# PowerLED_module.net
KiCad netlist of a schematic drawn in EAGLE
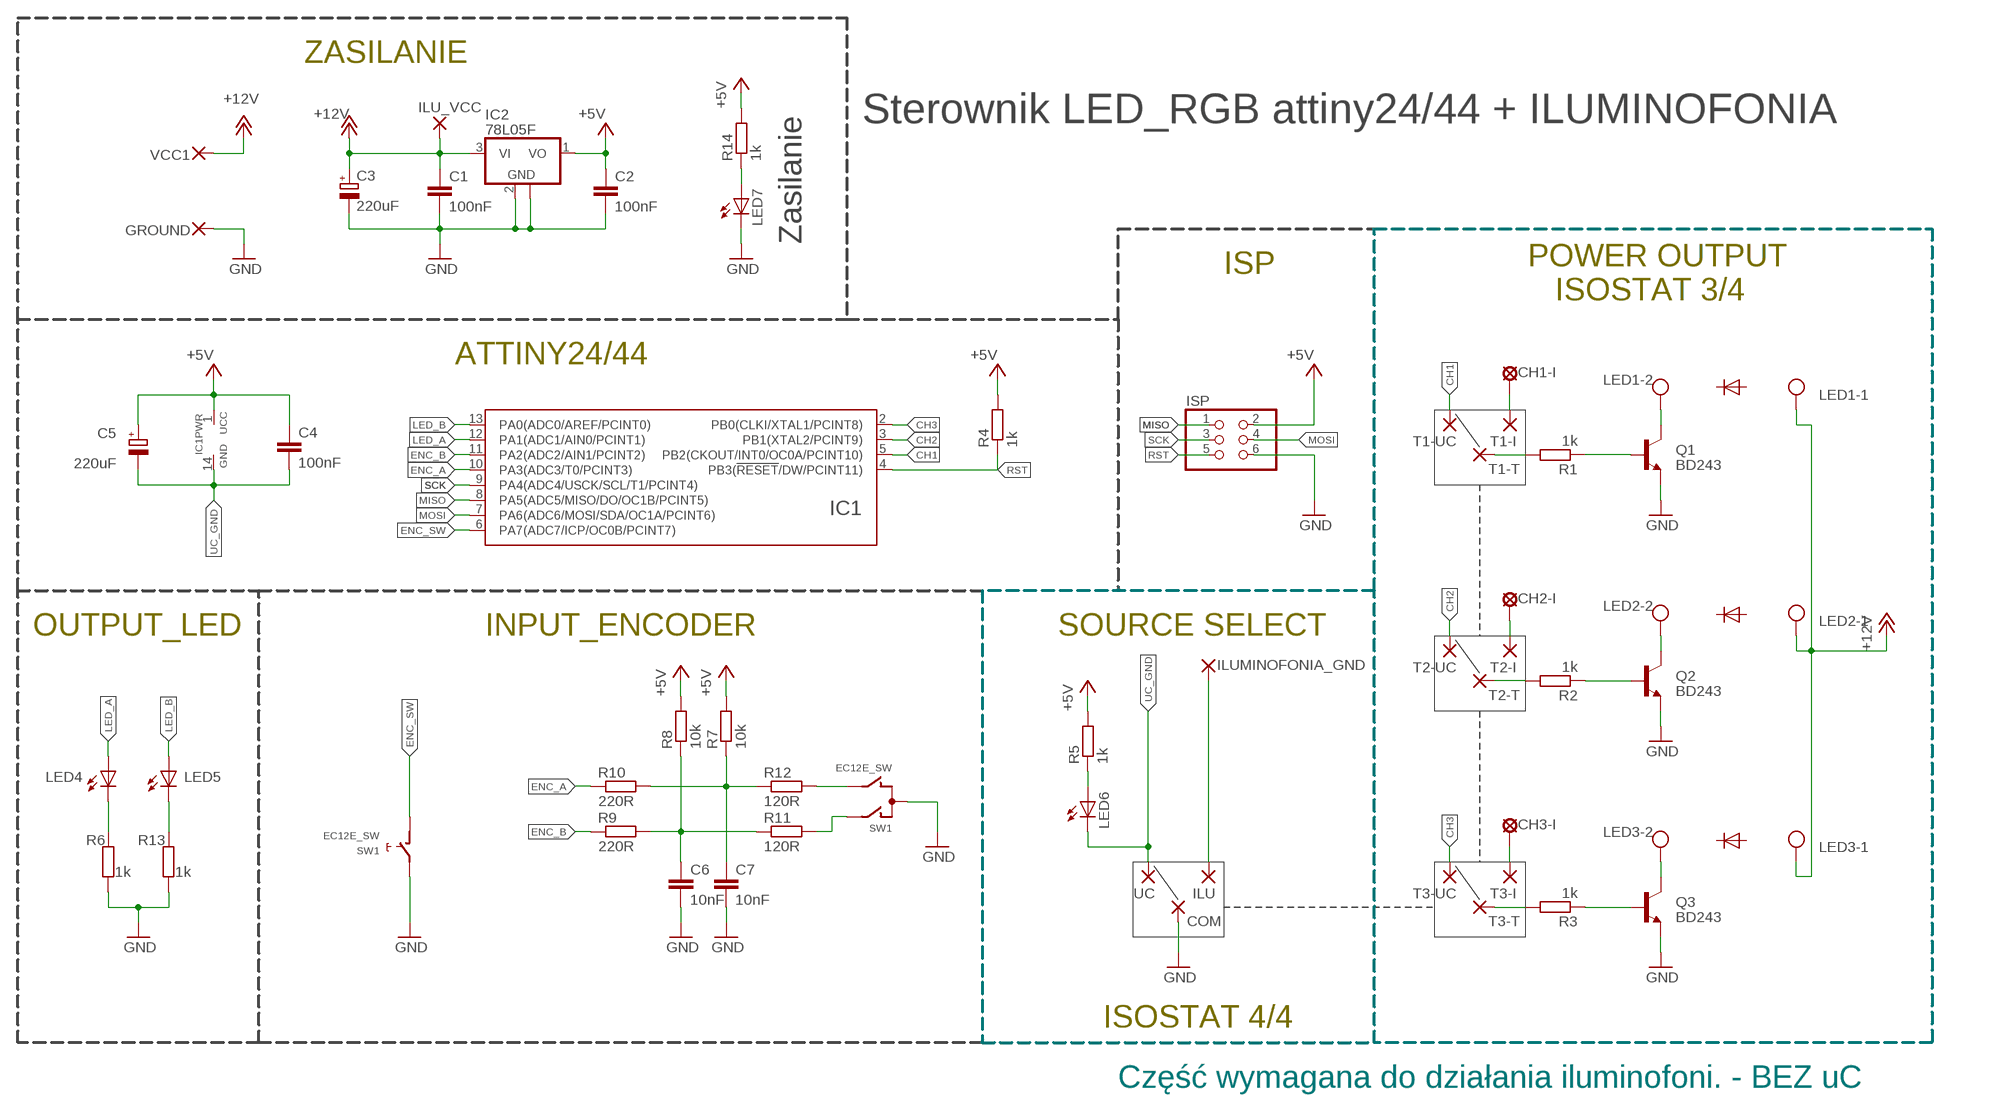
[diagram p0: schematic, sheet 1]

(export (version "E")
  (design (tool "Eeschema 10.0.6"))
  (components
    (comp (ref "C1")
      (value "100nF")
      (footprint "eagle-import:C50-45-75")
      (libsource (lib "eagle-import") (part "C-EU050-045-075"))
    )
    (comp (ref "C2")
      (value "100nF")
      (footprint "eagle-import:C50-45-75")
      (libsource (lib "eagle-import") (part "C-EU050-045-075"))
    )
    (comp (ref "C3")
      (value "220uF")
      (footprint "eagle-import:E2,5-6")
      (libsource (lib "eagle-import") (part "C-EU-POL'"))
    )
    (comp (ref "C4")
      (value "100nF")
      (footprint "eagle-import:C50-45-75")
      (libsource (lib "eagle-import") (part "C-EU050-045-075"))
    )
    (comp (ref "C5")
      (value "220uF")
      (footprint "eagle-import:E2,5-6")
      (libsource (lib "eagle-import") (part "C-EU-POL'"))
    )
    (comp (ref "C6")
      (value "10nF")
      (footprint "eagle-import:C50-45-75")
      (libsource (lib "eagle-import") (part "C-EU050-045-075"))
    )
    (comp (ref "C7")
      (value "10nF")
      (footprint "eagle-import:C50-45-75")
      (libsource (lib "eagle-import") (part "C-EU050-045-075"))
    )
    (comp (ref "CH1-I")
      (value "SE14")
      (footprint "eagle-import:SE14")
      (libsource (lib "eagle-import") (part "SE14"))
    )
    (comp (ref "CH2-I")
      (value "SE14")
      (footprint "eagle-import:SE14")
      (libsource (lib "eagle-import") (part "SE14"))
    )
    (comp (ref "CH3-I")
      (value "SE14")
      (footprint "eagle-import:SE14")
      (libsource (lib "eagle-import") (part "SE14"))
    )
    (comp (ref "COM")
      (value "1,6/0,9")
      (footprint "eagle-import:1,6_0,9")
      (libsource (lib "eagle-import") (part "1,6/0,9"))
    )
    (comp (ref "GROUND")
      (value "3,81/1,4")
      (footprint "eagle-import:3,81_1,4")
      (libsource (lib "eagle-import") (part "3,81/1,4"))
    )
    (comp (ref "IC1")
      (value "ATTINY24/44/84-SSU")
      (footprint "eagle-import:SOIC14")
      (libsource (lib "eagle-import") (part "ATTINY24/44/84-SSU"))
    )
    (comp (ref "IC2")
      (value "78L05F")
      (footprint "eagle-import:SOT89")
      (libsource (lib "eagle-import") (part "78LF05"))
    )
    (comp (ref "ILU")
      (value "1,6/0,9")
      (footprint "eagle-import:1,6_0,9")
      (libsource (lib "eagle-import") (part "1,6/0,9"))
    )
    (comp (ref "ILUMINOFONIA_GND")
      (value "3,81/1,4")
      (footprint "eagle-import:3,81_1,4")
      (libsource (lib "eagle-import") (part "3,81/1,4"))
    )
    (comp (ref "ILU_VCC")
      (value "3,81/1,4")
      (footprint "eagle-import:3,81_1,4")
      (libsource (lib "eagle-import") (part "3,81/1,4"))
    )
    (comp (ref "ISP")
      (value "PINHD-2X3")
      (footprint "eagle-import:2X03")
      (libsource (lib "eagle-import") (part "PINHD-2X3"))
    )
    (comp (ref "LED1")
      (value "AK300/2")
      (footprint "eagle-import:AK300_2")
      (libsource (lib "eagle-import") (part "AK300/2"))
    )
    (comp (ref "LED2")
      (value "AK300/2")
      (footprint "eagle-import:AK300_2")
      (libsource (lib "eagle-import") (part "AK300/2"))
    )
    (comp (ref "LED3")
      (value "AK300/2")
      (footprint "eagle-import:AK300_2")
      (libsource (lib "eagle-import") (part "AK300/2"))
    )
    (comp (ref "LED4")
      (value "LED5MM")
      (footprint "eagle-import:LED5MM")
      (libsource (lib "eagle-import") (part "LED5MM"))
    )
    (comp (ref "LED5")
      (value "LED5MM")
      (footprint "eagle-import:LED5MM")
      (libsource (lib "eagle-import") (part "LED5MM"))
    )
    (comp (ref "LED6")
      (value "LED5MM")
      (footprint "eagle-import:LED5MM")
      (libsource (lib "eagle-import") (part "LED5MM"))
    )
    (comp (ref "LED7")
      (value "LED5MM")
      (footprint "eagle-import:LED5MM")
      (libsource (lib "eagle-import") (part "LED5MM"))
    )
    (comp (ref "Q1")
      (value "BD243")
      (footprint "eagle-import:TO220")
      (libsource (lib "eagle-import") (part "BD243"))
    )
    (comp (ref "Q2")
      (value "BD243")
      (footprint "eagle-import:TO220")
      (libsource (lib "eagle-import") (part "BD243"))
    )
    (comp (ref "Q3")
      (value "BD243")
      (footprint "eagle-import:TO220")
      (libsource (lib "eagle-import") (part "BD243"))
    )
    (comp (ref "R1")
      (value "1k")
      (footprint "eagle-import:204_7")
      (libsource (lib "eagle-import") (part "R-EU7"))
    )
    (comp (ref "R2")
      (value "1k")
      (footprint "eagle-import:204_7")
      (libsource (lib "eagle-import") (part "R-EU7"))
    )
    (comp (ref "R3")
      (value "1k")
      (footprint "eagle-import:204_7")
      (libsource (lib "eagle-import") (part "R-EU7"))
    )
    (comp (ref "R4")
      (value "1k")
      (footprint "eagle-import:M1206")
      (libsource (lib "eagle-import") (part "R-EU_M1206"))
    )
    (comp (ref "R5")
      (value "1k")
      (footprint "eagle-import:204_7")
      (libsource (lib "eagle-import") (part "R-EU7"))
    )
    (comp (ref "R6")
      (value "1k")
      (footprint "eagle-import:204_7")
      (libsource (lib "eagle-import") (part "R-EU7"))
    )
    (comp (ref "R7")
      (value "10k")
      (footprint "eagle-import:M1206")
      (libsource (lib "eagle-import") (part "R-EU_M1206"))
    )
    (comp (ref "R8")
      (value "10k")
      (footprint "eagle-import:M1206")
      (libsource (lib "eagle-import") (part "R-EU_M1206"))
    )
    (comp (ref "R9")
      (value "220R")
      (footprint "eagle-import:M1206")
      (libsource (lib "eagle-import") (part "R-EU_M1206"))
    )
    (comp (ref "R10")
      (value "220R")
      (footprint "eagle-import:M1206")
      (libsource (lib "eagle-import") (part "R-EU_M1206"))
    )
    (comp (ref "R11")
      (value "120R")
      (footprint "eagle-import:M1206")
      (libsource (lib "eagle-import") (part "R-EU_M1206"))
    )
    (comp (ref "R12")
      (value "120R")
      (footprint "eagle-import:M1206")
      (libsource (lib "eagle-import") (part "R-EU_M1206"))
    )
    (comp (ref "R13")
      (value "1k")
      (footprint "eagle-import:204_7")
      (libsource (lib "eagle-import") (part "R-EU7"))
    )
    (comp (ref "R14")
      (value "1k")
      (footprint "eagle-import:204_7")
      (libsource (lib "eagle-import") (part "R-EU7"))
    )
    (comp (ref "SW1")
      (value "EC12E_SW")
      (footprint "eagle-import:ALPS_EC12E_SW")
      (fields (field (name "MPN") "EC12E2424407"))
      (libsource (lib "eagle-import") (part "EC12E_SW"))
    )
    (comp (ref "T1-I")
      (value "1,6/0,9")
      (footprint "eagle-import:1,6_0,9")
      (libsource (lib "eagle-import") (part "1,6/0,9"))
    )
    (comp (ref "T1-T")
      (value "1,6/0,9")
      (footprint "eagle-import:1,6_0,9")
      (libsource (lib "eagle-import") (part "1,6/0,9"))
    )
    (comp (ref "T1-UC")
      (value "1,6/0,9")
      (footprint "eagle-import:1,6_0,9")
      (libsource (lib "eagle-import") (part "1,6/0,9"))
    )
    (comp (ref "T2-I")
      (value "1,6/0,9")
      (footprint "eagle-import:1,6_0,9")
      (libsource (lib "eagle-import") (part "1,6/0,9"))
    )
    (comp (ref "T2-T")
      (value "1,6/0,9")
      (footprint "eagle-import:1,6_0,9")
      (libsource (lib "eagle-import") (part "1,6/0,9"))
    )
    (comp (ref "T2-UC")
      (value "1,6/0,9")
      (footprint "eagle-import:1,6_0,9")
      (libsource (lib "eagle-import") (part "1,6/0,9"))
    )
    (comp (ref "T3-I")
      (value "1,6/0,9")
      (footprint "eagle-import:1,6_0,9")
      (libsource (lib "eagle-import") (part "1,6/0,9"))
    )
    (comp (ref "T3-T")
      (value "1,6/0,9")
      (footprint "eagle-import:1,6_0,9")
      (libsource (lib "eagle-import") (part "1,6/0,9"))
    )
    (comp (ref "T3-UC")
      (value "1,6/0,9")
      (footprint "eagle-import:1,6_0,9")
      (libsource (lib "eagle-import") (part "1,6/0,9"))
    )
    (comp (ref "UC")
      (value "1,6/0,9")
      (footprint "eagle-import:1,6_0,9")
      (libsource (lib "eagle-import") (part "1,6/0,9"))
    )
    (comp (ref "VCC1")
      (value "3,81/1,4")
      (footprint "eagle-import:3,81_1,4")
      (libsource (lib "eagle-import") (part "3,81/1,4"))
    )
  )
  (nets
    (net (code "1") (name "+5V") (class "Default")
      (node (ref "C2") (pin "P$1") (pinfunction "1_P$1") (pintype "passive"))
      (node (ref "C4") (pin "P$1") (pinfunction "1_P$1") (pintype "passive"))
      (node (ref "C5") (pin "P$1") (pinfunction "+_P$1") (pintype "passive"))
      (node (ref "IC1") (pin "1") (pinfunction "UCC_1") (pintype "power_in"))
      (node (ref "IC2") (pin "1") (pinfunction "VO_1") (pintype "passive"))
      (node (ref "ISP") (pin "2") (pinfunction "2_2") (pintype "passive"))
      (node (ref "R14") (pin "P$2") (pinfunction "2_P$2") (pintype "passive"))
      (node (ref "R4") (pin "2") (pinfunction "2_2") (pintype "passive"))
      (node (ref "R5") (pin "P$2") (pinfunction "2_P$2") (pintype "passive"))
      (node (ref "R7") (pin "2") (pinfunction "2_2") (pintype "passive"))
      (node (ref "R8") (pin "2") (pinfunction "2_2") (pintype "passive"))
    )
    (net (code "2") (name "+12V") (class "Default")
      (node (ref "C1") (pin "P$1") (pinfunction "1_P$1") (pintype "passive"))
      (node (ref "C3") (pin "P$1") (pinfunction "+_P$1") (pintype "passive"))
      (node (ref "IC2") (pin "3") (pinfunction "VI_3") (pintype "input"))
      (node (ref "ILU_VCC") (pin "1") (pinfunction "P_1") (pintype "passive"))
      (node (ref "LED1") (pin "1") (pinfunction "KL_1") (pintype "passive"))
      (node (ref "LED2") (pin "1") (pinfunction "KL_1") (pintype "passive"))
      (node (ref "LED3") (pin "1") (pinfunction "KL_1") (pintype "passive"))
      (node (ref "VCC1") (pin "1") (pinfunction "P_1") (pintype "passive"))
    )
    (net (code "3") (name "CH1") (class "Default")
      (node (ref "IC1") (pin "5") (pinfunction "PB2(CKOUT/INT0/OC0A/PCINT10)_5") (pintype "bidirectional"))
      (node (ref "T1-UC") (pin "1") (pinfunction "P_1") (pintype "passive"))
    )
    (net (code "4") (name "CH2") (class "Default")
      (node (ref "IC1") (pin "3") (pinfunction "PB1(XTAL2/PCINT9)_3") (pintype "bidirectional"))
      (node (ref "T2-UC") (pin "1") (pinfunction "P_1") (pintype "passive"))
    )
    (net (code "5") (name "CH3") (class "Default")
      (node (ref "IC1") (pin "2") (pinfunction "PB0(CLKI/XTAL1/PCINT8)_2") (pintype "bidirectional"))
      (node (ref "T3-UC") (pin "1") (pinfunction "P_1") (pintype "passive"))
    )
    (net (code "6") (name "ENC_A") (class "Default")
      (node (ref "IC1") (pin "10") (pinfunction "PA3(ADC3/T0/PCINT3)_10") (pintype "bidirectional"))
      (node (ref "R10") (pin "1") (pinfunction "1_1") (pintype "passive"))
    )
    (net (code "7") (name "ENC_B") (class "Default")
      (node (ref "IC1") (pin "11") (pinfunction "PA2(ADC2/AIN1/PCINT2)_11") (pintype "bidirectional"))
      (node (ref "R9") (pin "1") (pinfunction "1_1") (pintype "passive"))
    )
    (net (code "8") (name "ENC_SW") (class "Default")
      (node (ref "IC1") (pin "6") (pinfunction "PA7(ADC7/ICP/OC0B/PCINT7)_6") (pintype "bidirectional"))
      (node (ref "SW1") (pin "D") (pinfunction "1_D") (pintype "passive"))
    )
    (net (code "9") (name "GND") (class "Default")
      (node (ref "C1") (pin "P$2") (pinfunction "2_P$2") (pintype "passive"))
      (node (ref "C2") (pin "P$2") (pinfunction "2_P$2") (pintype "passive"))
      (node (ref "C3") (pin "P$2") (pinfunction "-_P$2") (pintype "passive"))
      (node (ref "C6") (pin "P$2") (pinfunction "2_P$2") (pintype "passive"))
      (node (ref "C7") (pin "P$2") (pinfunction "2_P$2") (pintype "passive"))
      (node (ref "COM") (pin "1") (pinfunction "P_1") (pintype "passive"))
      (node (ref "GROUND") (pin "1") (pinfunction "P_1") (pintype "passive"))
      (node (ref "IC2") (pin "2") (pinfunction "GND_2") (pintype "passive"))
      (node (ref "IC2") (pin "2@1") (pinfunction "GND_2@1") (pintype "passive"))
      (node (ref "ISP") (pin "6") (pinfunction "6_6") (pintype "passive"))
      (node (ref "LED7") (pin "K") (pinfunction "C_K") (pintype "passive"))
      (node (ref "Q1") (pin "3") (pinfunction "E_3") (pintype "passive"))
      (node (ref "Q2") (pin "3") (pinfunction "E_3") (pintype "passive"))
      (node (ref "Q3") (pin "3") (pinfunction "E_3") (pintype "passive"))
      (node (ref "R13") (pin "P$1") (pinfunction "1_P$1") (pintype "passive"))
      (node (ref "R6") (pin "P$1") (pinfunction "1_P$1") (pintype "passive"))
      (node (ref "SW1") (pin "C") (pinfunction "C_C") (pintype "passive"))
      (node (ref "SW1") (pin "E") (pinfunction "2_E") (pintype "passive"))
    )
    (net (code "10") (name "LED_A") (class "Default")
      (node (ref "IC1") (pin "12") (pinfunction "PA1(ADC1/AIN0/PCINT1)_12") (pintype "bidirectional"))
      (node (ref "LED4") (pin "A") (pinfunction "A_A") (pintype "passive"))
    )
    (net (code "11") (name "LED_B") (class "Default")
      (node (ref "IC1") (pin "13") (pinfunction "PA0(ADC0/AREF/PCINT0)_13") (pintype "bidirectional"))
      (node (ref "LED5") (pin "A") (pinfunction "A_A") (pintype "passive"))
    )
    (net (code "12") (name "MISO") (class "Default")
      (node (ref "IC1") (pin "8") (pinfunction "PA5(ADC5/MISO/DO/OC1B/PCINT5)_8") (pintype "bidirectional"))
      (node (ref "ISP") (pin "1") (pinfunction "1_1") (pintype "passive"))
    )
    (net (code "13") (name "MOSI") (class "Default")
      (node (ref "IC1") (pin "7") (pinfunction "PA6(ADC6/MOSI/SDA/OC1A/PCINT6)_7") (pintype "bidirectional"))
      (node (ref "ISP") (pin "4") (pinfunction "4_4") (pintype "passive"))
    )
    (net (code "14") (name "Net-(C6-1)") (class "Default")
      (node (ref "C6") (pin "P$1") (pinfunction "1_P$1") (pintype "passive"))
      (node (ref "R11") (pin "1") (pinfunction "1_1") (pintype "passive"))
      (node (ref "R8") (pin "1") (pinfunction "1_1") (pintype "passive"))
      (node (ref "R9") (pin "2") (pinfunction "2_2") (pintype "passive"))
    )
    (net (code "15") (name "Net-(C7-1)") (class "Default")
      (node (ref "C7") (pin "P$1") (pinfunction "1_P$1") (pintype "passive"))
      (node (ref "R10") (pin "2") (pinfunction "2_2") (pintype "passive"))
      (node (ref "R12") (pin "1") (pinfunction "1_1") (pintype "passive"))
      (node (ref "R7") (pin "1") (pinfunction "1_1") (pintype "passive"))
    )
    (net (code "16") (name "Net-(ILU-P)") (class "Default")
      (node (ref "ILU") (pin "1") (pinfunction "P_1") (pintype "passive"))
      (node (ref "ILUMINOFONIA_GND") (pin "1") (pinfunction "P_1") (pintype "passive"))
    )
    (net (code "17") (name "Net-(LED1B-KL)") (class "Default")
      (node (ref "LED1") (pin "2") (pinfunction "KL_2") (pintype "passive"))
      (node (ref "Q1") (pin "2") (pinfunction "C_2") (pintype "passive"))
    )
    (net (code "18") (name "Net-(LED2B-KL)") (class "Default")
      (node (ref "LED2") (pin "2") (pinfunction "KL_2") (pintype "passive"))
      (node (ref "Q2") (pin "2") (pinfunction "C_2") (pintype "passive"))
    )
    (net (code "19") (name "Net-(LED3B-KL)") (class "Default")
      (node (ref "LED3") (pin "2") (pinfunction "KL_2") (pintype "passive"))
      (node (ref "Q3") (pin "2") (pinfunction "C_2") (pintype "passive"))
    )
    (net (code "20") (name "Net-(LED4-C)") (class "Default")
      (node (ref "LED4") (pin "K") (pinfunction "C_K") (pintype "passive"))
      (node (ref "R6") (pin "P$2") (pinfunction "2_P$2") (pintype "passive"))
    )
    (net (code "21") (name "Net-(LED5-C)") (class "Default")
      (node (ref "LED5") (pin "K") (pinfunction "C_K") (pintype "passive"))
      (node (ref "R13") (pin "P$2") (pinfunction "2_P$2") (pintype "passive"))
    )
    (net (code "22") (name "Net-(Q1-B)") (class "Default")
      (node (ref "Q1") (pin "1") (pinfunction "B_1") (pintype "passive"))
      (node (ref "R1") (pin "P$1") (pinfunction "1_P$1") (pintype "passive"))
    )
    (net (code "23") (name "Net-(Q2-B)") (class "Default")
      (node (ref "Q2") (pin "1") (pinfunction "B_1") (pintype "passive"))
      (node (ref "R2") (pin "P$1") (pinfunction "1_P$1") (pintype "passive"))
    )
    (net (code "24") (name "Net-(Q3-B)") (class "Default")
      (node (ref "Q3") (pin "1") (pinfunction "B_1") (pintype "passive"))
      (node (ref "R3") (pin "P$1") (pinfunction "1_P$1") (pintype "passive"))
    )
    (net (code "25") (name "Net-(R1-2)") (class "Default")
      (node (ref "R1") (pin "P$2") (pinfunction "2_P$2") (pintype "passive"))
      (node (ref "T1-T") (pin "1") (pinfunction "P_1") (pintype "passive"))
    )
    (net (code "26") (name "Net-(R2-2)") (class "Default")
      (node (ref "R2") (pin "P$2") (pinfunction "2_P$2") (pintype "passive"))
      (node (ref "T2-T") (pin "1") (pinfunction "P_1") (pintype "passive"))
    )
    (net (code "27") (name "Net-(R3-2)") (class "Default")
      (node (ref "R3") (pin "P$2") (pinfunction "2_P$2") (pintype "passive"))
      (node (ref "T3-T") (pin "1") (pinfunction "P_1") (pintype "passive"))
    )
    (net (code "28") (name "Net-(R5-1)") (class "Default")
      (node (ref "LED6") (pin "A") (pinfunction "A_A") (pintype "passive"))
      (node (ref "R5") (pin "P$1") (pinfunction "1_P$1") (pintype "passive"))
    )
    (net (code "29") (name "Net-(R11-Pad2)") (class "Default")
      (node (ref "R11") (pin "2") (pinfunction "2_2") (pintype "passive"))
      (node (ref "SW1") (pin "A") (pinfunction "A_A") (pintype "passive"))
    )
    (net (code "30") (name "Net-(R12-Pad2)") (class "Default")
      (node (ref "R12") (pin "2") (pinfunction "2_2") (pintype "passive"))
      (node (ref "SW1") (pin "B") (pinfunction "B_B") (pintype "passive"))
    )
    (net (code "31") (name "Net-(R14-1)") (class "Default")
      (node (ref "LED7") (pin "A") (pinfunction "A_A") (pintype "passive"))
      (node (ref "R14") (pin "P$1") (pinfunction "1_P$1") (pintype "passive"))
    )
    (net (code "32") (name "Net-(T1-I-P)") (class "Default")
      (node (ref "CH1-I") (pin "MP") (pinfunction "MP_MP") (pintype "passive"))
      (node (ref "T1-I") (pin "1") (pinfunction "P_1") (pintype "passive"))
    )
    (net (code "33") (name "Net-(T2-I-P)") (class "Default")
      (node (ref "CH2-I") (pin "MP") (pinfunction "MP_MP") (pintype "passive"))
      (node (ref "T2-I") (pin "1") (pinfunction "P_1") (pintype "passive"))
    )
    (net (code "34") (name "Net-(T3-I-P)") (class "Default")
      (node (ref "CH3-I") (pin "MP") (pinfunction "MP_MP") (pintype "passive"))
      (node (ref "T3-I") (pin "1") (pinfunction "P_1") (pintype "passive"))
    )
    (net (code "35") (name "RST") (class "Default")
      (node (ref "IC1") (pin "4") (pinfunction "PB3(~{RESET}/DW/PCINT11)_4") (pintype "bidirectional"))
      (node (ref "ISP") (pin "5") (pinfunction "5_5") (pintype "passive"))
      (node (ref "R4") (pin "1") (pinfunction "1_1") (pintype "passive"))
    )
    (net (code "36") (name "SCK") (class "Default")
      (node (ref "IC1") (pin "9") (pinfunction "PA4(ADC4/USCK/SCL/T1/PCINT4)_9") (pintype "bidirectional"))
      (node (ref "ISP") (pin "3") (pinfunction "3_3") (pintype "passive"))
    )
    (net (code "37") (name "UC_GND") (class "Default")
      (node (ref "C4") (pin "P$2") (pinfunction "2_P$2") (pintype "passive"))
      (node (ref "C5") (pin "P$2") (pinfunction "-_P$2") (pintype "passive"))
      (node (ref "IC1") (pin "14") (pinfunction "GND_14") (pintype "power_in"))
      (node (ref "LED6") (pin "K") (pinfunction "C_K") (pintype "passive"))
      (node (ref "UC") (pin "1") (pinfunction "P_1") (pintype "passive"))
    )
  )
)
